# Remote_Core.net
KiCad netlist of a schematic drawn in Altium Designer
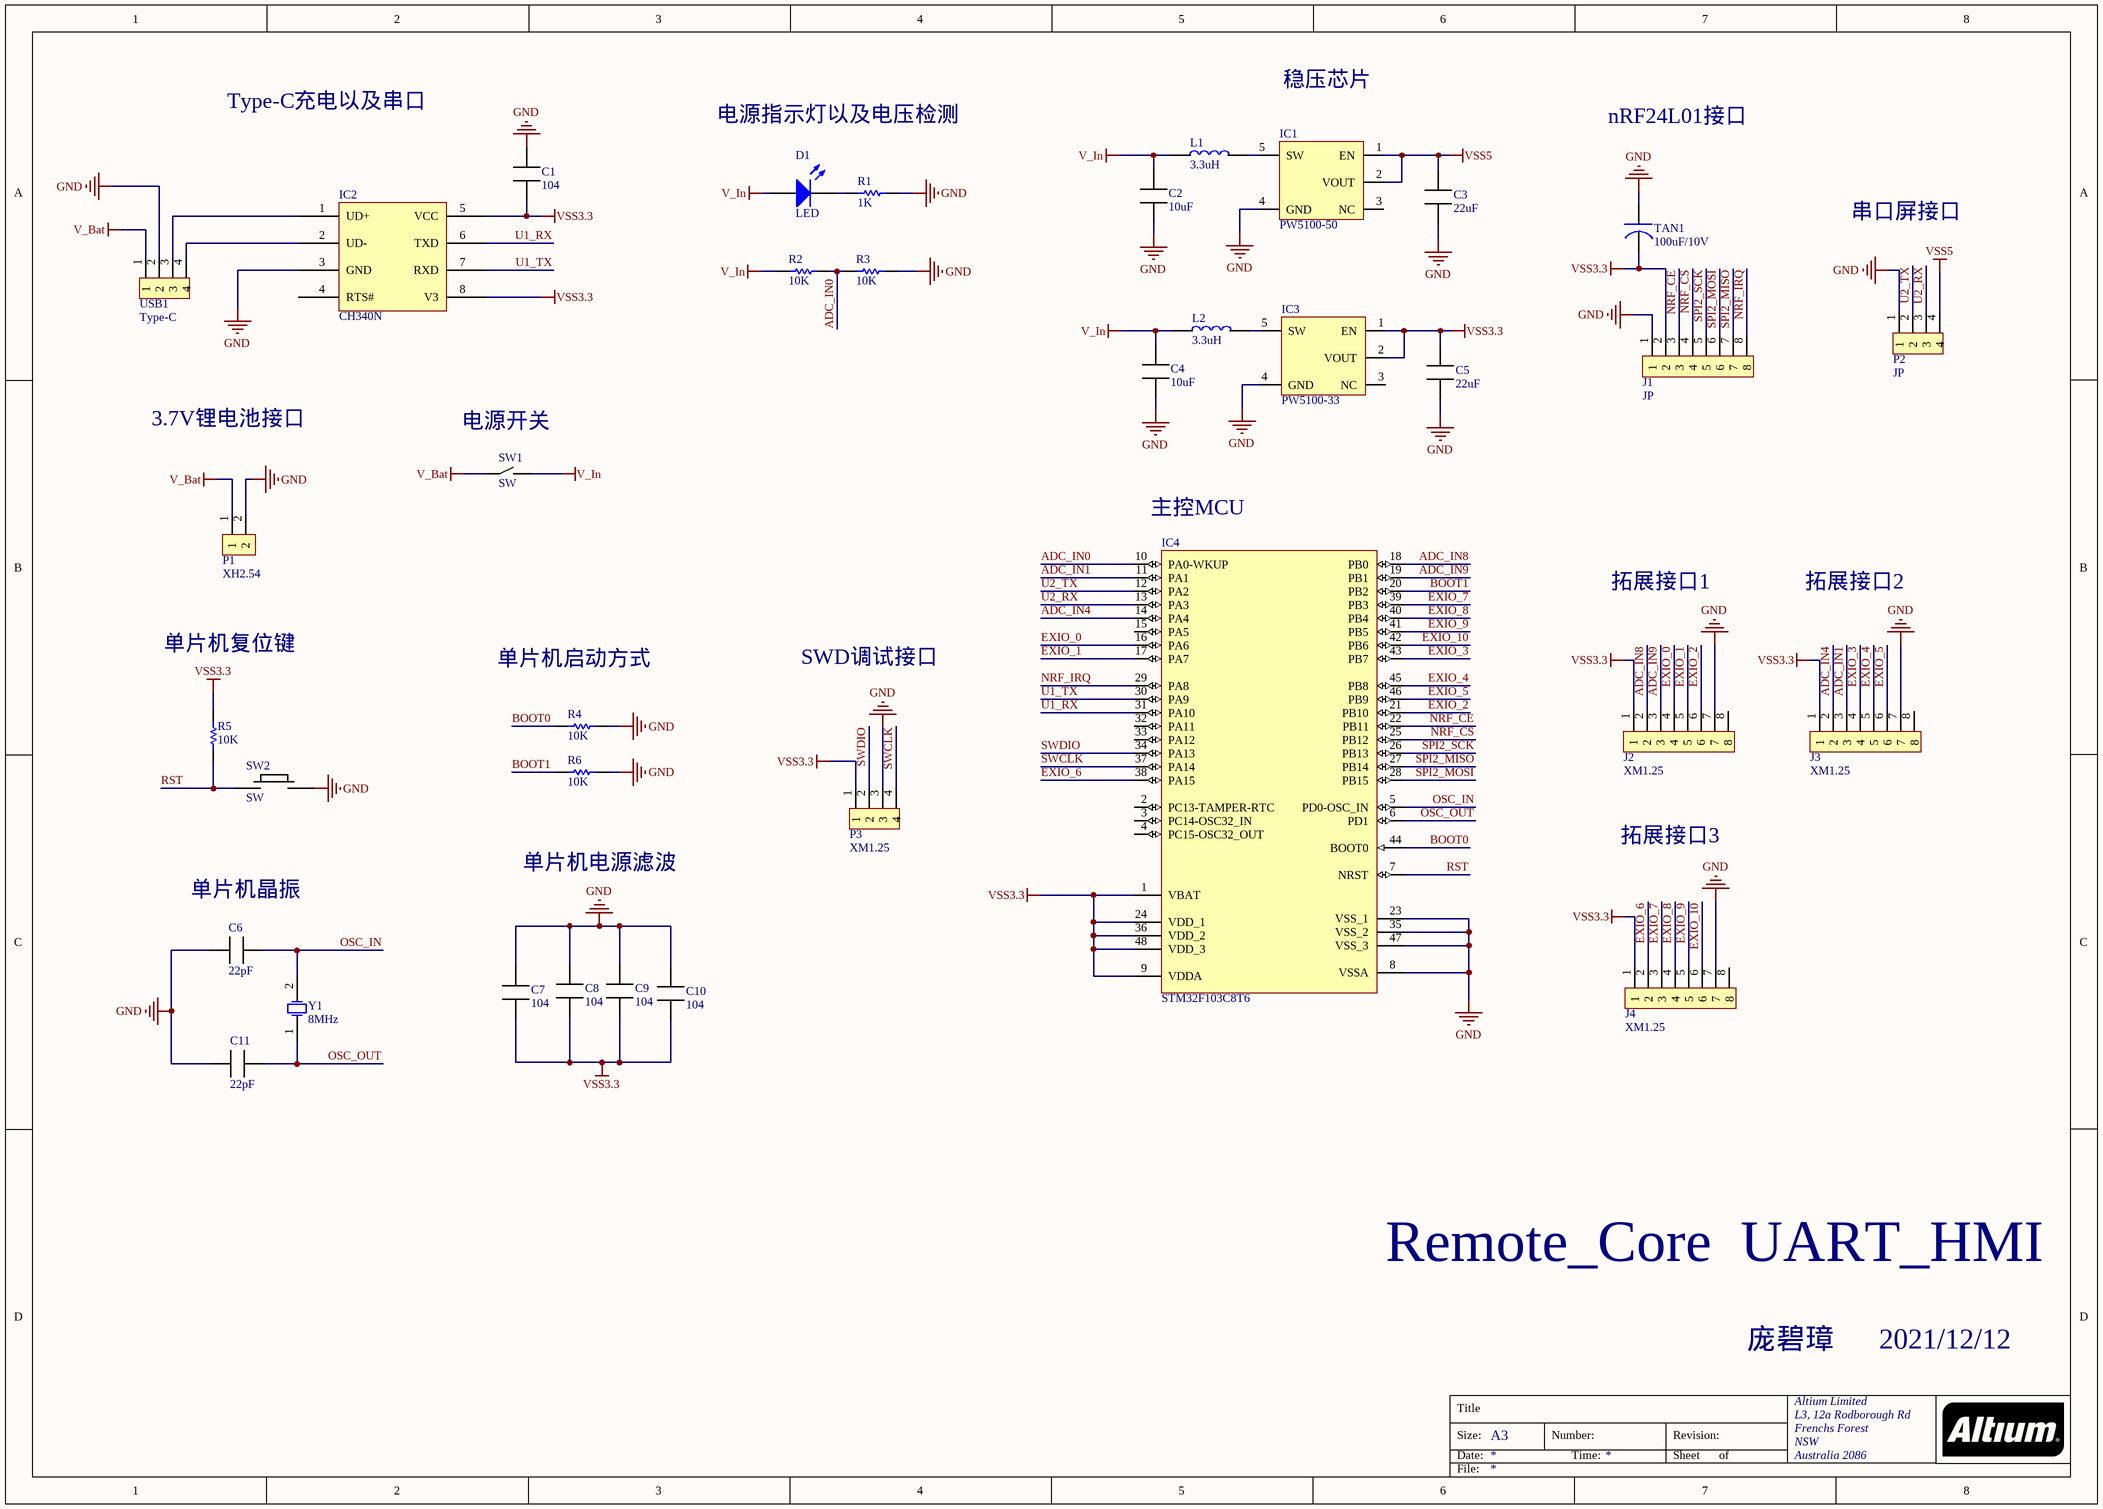
[diagram p0: Remote_Core.SchDoc]

(export (version "E")
  (design (tool "Eeschema 10.0.6"))
  (components
    (comp (ref "C1") (value "104") (footprint "C 0603") (libsource (lib "Remote") (part "电容")))
    (comp (ref "C2")
      (value "10uF")
      (footprint "C 0603")
      (libsource (lib "altium-import") (part "root_1_电容_"))
    )
    (comp (ref "C3") (value "22uF") (footprint "C 0603") (libsource (lib "Remote") (part "电容")))
    (comp (ref "C4")
      (value "10uF")
      (footprint "C 0603")
      (libsource (lib "altium-import") (part "root_1_电容_"))
    )
    (comp (ref "C5") (value "22uF") (footprint "C 0603") (libsource (lib "Remote") (part "电容")))
    (comp (ref "C6")
      (value "22pF")
      (footprint "C 0603")
      (libsource (lib "altium-import") (part "root_0_电容_"))
    )
    (comp (ref "C7") (value "104") (footprint "C 0603") (libsource (lib "Remote") (part "电容")))
    (comp (ref "C8") (value "104") (footprint "C 0603") (libsource (lib "Remote") (part "电容")))
    (comp (ref "C9") (value "104") (footprint "C 0603") (libsource (lib "Remote") (part "电容")))
    (comp (ref "C10") (value "104") (footprint "C 0603") (libsource (lib "Remote") (part "电容")))
    (comp (ref "C11")
      (value "22pF")
      (footprint "C 0603")
      (libsource (lib "altium-import") (part "root_0_电容_"))
    )
    (comp (ref "D1")
      (value "LED")
      (footprint "LED 0603")
      (description "Typical INFRARED GaAs LED")
      (fields (field (name "PUBLISHER") "Altium Limited"))
      (libsource (lib "Remote") (part "LED"))
    )
    (comp (ref "IC1")
      (value "PW5100-50")
      (footprint "PW5100")
      (libsource (lib "altium-import") (part "root_0_PW5100_"))
    )
    (comp (ref "IC2")
      (value "CH340N")
      (footprint "SOP-8")
      (libsource (lib "altium-import") (part "root_0_CH340N_"))
    )
    (comp (ref "IC3")
      (value "PW5100-33")
      (footprint "PW5100")
      (libsource (lib "altium-import") (part "root_0_PW5100_"))
    )
    (comp (ref "IC4")
      (value "STM32F103C8T6")
      (footprint "LQPF48 7X7")
      (libsource (lib "altium-import") (part "root_0_stm32f103c8t6_"))
    )
    (comp (ref "J1")
      (value "JP")
      (footprint "HDR2.54-LI-2x4P")
      (libsource (lib "altium-import") (part "root_0_1X8排针_"))
    )
    (comp (ref "J2")
      (value "XM1.25")
      (footprint "MX1.25 8P")
      (libsource (lib "altium-import") (part "root_0_1X8排针_"))
    )
    (comp (ref "J3")
      (value "XM1.25")
      (footprint "MX1.25 8P")
      (libsource (lib "altium-import") (part "root_0_1X8排针_"))
    )
    (comp (ref "J4")
      (value "XM1.25")
      (footprint "MX1.25 8P")
      (libsource (lib "altium-import") (part "root_0_1X8排针_"))
    )
    (comp (ref "L1") (value "3.3uH") (footprint "0630") (libsource (lib "Remote") (part "电感")))
    (comp (ref "L2") (value "3.3uH") (footprint "0630") (libsource (lib "Remote") (part "电感")))
    (comp (ref "P1") (value "XH2.54") (footprint "XH2.54 2P") (libsource (lib "Remote") (part "1X2排针")))
    (comp (ref "P2") (value "JP") (footprint "2.54 _ 4Pin") (libsource (lib "Remote") (part "1X4排针")))
    (comp (ref "P3")
      (value "XM1.25")
      (footprint "MX1.25")
      (libsource (lib "altium-import") (part "root_0_1X4排针_"))
    )
    (comp (ref "R1")
      (value "1K")
      (footprint "R 0603")
      (description "Resistor")
      (fields (field (name "PUBLISHER") "Altium Limited"))
      (libsource (lib "Remote") (part "Res"))
    )
    (comp (ref "R2")
      (value "10K")
      (footprint "R 0603")
      (description "Resistor")
      (fields (field (name "PUBLISHER") "Altium Limited"))
      (libsource (lib "Remote") (part "Res"))
    )
    (comp (ref "R3")
      (value "10K")
      (footprint "R 0603")
      (description "Resistor")
      (fields (field (name "PUBLISHER") "Altium Limited"))
      (libsource (lib "Remote") (part "Res"))
    )
    (comp (ref "R4")
      (value "10K")
      (footprint "R 0603")
      (description "Resistor")
      (fields (field (name "PUBLISHER") "Altium Limited"))
      (libsource (lib "altium-import") (part "root_0_Res_"))
    )
    (comp (ref "R5")
      (value "10K")
      (footprint "R 0603")
      (description "Resistor")
      (fields (field (name "PUBLISHER") "Altium Limited"))
      (libsource (lib "altium-import") (part "root_1_Res_"))
    )
    (comp (ref "R6")
      (value "10K")
      (footprint "R 0603")
      (description "Resistor")
      (fields (field (name "PUBLISHER") "Altium Limited"))
      (libsource (lib "altium-import") (part "root_0_Res_"))
    )
    (comp (ref "SW1") (value "SW") (footprint "拨动开关 9X3.5X3.5 侧卧") (libsource (lib "Remote") (part "开关")))
    (comp (ref "SW2")
      (value "SW")
      (footprint "SW SMD 3x6x2.5")
      (libsource (lib "altium-import") (part "root_0_弹簧开关_"))
    )
    (comp (ref "TAN1")
      (value "100uF/10V")
      (footprint "6.3*5.4mm 电解电容")
      (libsource (lib "Remote") (part "极性电容"))
    )
    (comp (ref "USB1")
      (value "Type-C")
      (footprint "USB Type-C")
      (libsource (lib "altium-import") (part "root_0_1X4排针_"))
    )
    (comp (ref "Y1")
      (value "8MHz")
      (footprint "OSC SMD")
      (description "Crystal Oscillator")
      (fields (field (name "PUBLISHER") "Altium Limited"))
      (libsource (lib "altium-import") (part "root_1_晶振_"))
    )
  )
  (nets
    (net (code "1") (name "/ADC_IN0") (class "Default")
      (node (ref "IC4") (pin "10") (pinfunction "PA0-WKUP_10") (pintype "bidirectional"))
      (node (ref "R2") (pin "2") (pinfunction "2_2") (pintype "passive"))
      (node (ref "R3") (pin "1") (pinfunction "1_1") (pintype "passive"))
    )
    (net (code "2") (name "/ADC_IN1") (class "Default")
      (node (ref "IC4") (pin "11") (pinfunction "PA1_11") (pintype "bidirectional"))
      (node (ref "J3") (pin "3") (pinfunction "3_3") (pintype "passive"))
    )
    (net (code "3") (name "/ADC_IN4") (class "Default")
      (node (ref "IC4") (pin "14") (pinfunction "PA4_14") (pintype "bidirectional"))
      (node (ref "J3") (pin "2") (pinfunction "2_2") (pintype "passive"))
    )
    (net (code "4") (name "/ADC_IN8") (class "Default")
      (node (ref "IC4") (pin "18") (pinfunction "PB0_18") (pintype "bidirectional"))
      (node (ref "J2") (pin "2") (pinfunction "2_2") (pintype "passive"))
    )
    (net (code "5") (name "/ADC_IN9") (class "Default")
      (node (ref "IC4") (pin "19") (pinfunction "PB1_19") (pintype "bidirectional"))
      (node (ref "J2") (pin "3") (pinfunction "3_3") (pintype "passive"))
    )
    (net (code "6") (name "/BOOT0") (class "Default")
      (node (ref "IC4") (pin "44") (pinfunction "BOOT0_44") (pintype "input"))
      (node (ref "R4") (pin "1") (pinfunction "1_1") (pintype "passive"))
    )
    (net (code "7") (name "/BOOT1") (class "Default")
      (node (ref "IC4") (pin "20") (pinfunction "PB2_20") (pintype "bidirectional"))
      (node (ref "R6") (pin "1") (pinfunction "1_1") (pintype "passive"))
    )
    (net (code "8") (name "/EXIO_0") (class "Default")
      (node (ref "IC4") (pin "16") (pinfunction "PA6_16") (pintype "bidirectional"))
      (node (ref "J2") (pin "4") (pinfunction "4_4") (pintype "passive"))
    )
    (net (code "9") (name "/EXIO_1") (class "Default")
      (node (ref "IC4") (pin "17") (pinfunction "PA7_17") (pintype "bidirectional"))
      (node (ref "J2") (pin "5") (pinfunction "5_5") (pintype "passive"))
    )
    (net (code "10") (name "/EXIO_2") (class "Default")
      (node (ref "IC4") (pin "21") (pinfunction "PB10_21") (pintype "bidirectional"))
      (node (ref "J2") (pin "6") (pinfunction "6_6") (pintype "passive"))
    )
    (net (code "11") (name "/EXIO_3") (class "Default")
      (node (ref "IC4") (pin "43") (pinfunction "PB7_43") (pintype "bidirectional"))
      (node (ref "J3") (pin "4") (pinfunction "4_4") (pintype "passive"))
    )
    (net (code "12") (name "/EXIO_4") (class "Default")
      (node (ref "IC4") (pin "45") (pinfunction "PB8_45") (pintype "bidirectional"))
      (node (ref "J3") (pin "5") (pinfunction "5_5") (pintype "passive"))
    )
    (net (code "13") (name "/EXIO_5") (class "Default")
      (node (ref "IC4") (pin "46") (pinfunction "PB9_46") (pintype "bidirectional"))
      (node (ref "J3") (pin "6") (pinfunction "6_6") (pintype "passive"))
    )
    (net (code "14") (name "/EXIO_6") (class "Default")
      (node (ref "IC4") (pin "38") (pinfunction "PA15_38") (pintype "bidirectional"))
      (node (ref "J4") (pin "2") (pinfunction "2_2") (pintype "passive"))
    )
    (net (code "15") (name "/EXIO_7") (class "Default")
      (node (ref "IC4") (pin "39") (pinfunction "PB3_39") (pintype "bidirectional"))
      (node (ref "J4") (pin "3") (pinfunction "3_3") (pintype "passive"))
    )
    (net (code "16") (name "/EXIO_8") (class "Default")
      (node (ref "IC4") (pin "40") (pinfunction "PB4_40") (pintype "bidirectional"))
      (node (ref "J4") (pin "4") (pinfunction "4_4") (pintype "passive"))
    )
    (net (code "17") (name "/EXIO_9") (class "Default")
      (node (ref "IC4") (pin "41") (pinfunction "PB5_41") (pintype "bidirectional"))
      (node (ref "J4") (pin "5") (pinfunction "5_5") (pintype "passive"))
    )
    (net (code "18") (name "/EXIO_10") (class "Default")
      (node (ref "IC4") (pin "42") (pinfunction "PB6_42") (pintype "bidirectional"))
      (node (ref "J4") (pin "6") (pinfunction "6_6") (pintype "passive"))
    )
    (net (code "19") (name "/NRF_CE") (class "Default")
      (node (ref "IC4") (pin "22") (pinfunction "PB11_22") (pintype "bidirectional"))
      (node (ref "J1") (pin "3") (pinfunction "3_3") (pintype "passive"))
    )
    (net (code "20") (name "/NRF_CS") (class "Default")
      (node (ref "IC4") (pin "25") (pinfunction "PB12_25") (pintype "bidirectional"))
      (node (ref "J1") (pin "4") (pinfunction "4_4") (pintype "passive"))
    )
    (net (code "21") (name "/NRF_IRQ") (class "Default")
      (node (ref "IC4") (pin "29") (pinfunction "PA8_29") (pintype "bidirectional"))
      (node (ref "J1") (pin "8") (pinfunction "8_8") (pintype "passive"))
    )
    (net (code "22") (name "/OSC_IN") (class "Default")
      (node (ref "C6") (pin "2") (pinfunction "2_2") (pintype "passive"))
      (node (ref "IC4") (pin "5") (pinfunction "PD0-OSC_IN_5") (pintype "bidirectional"))
      (node (ref "Y1") (pin "2") (pinfunction "OSC2_2") (pintype "passive"))
    )
    (net (code "23") (name "/OSC_OUT") (class "Default")
      (node (ref "C11") (pin "2") (pinfunction "2_2") (pintype "passive"))
      (node (ref "IC4") (pin "6") (pinfunction "PD1_6") (pintype "bidirectional"))
      (node (ref "Y1") (pin "1") (pinfunction "OSC1_1") (pintype "passive"))
    )
    (net (code "24") (name "/RST") (class "Default")
      (node (ref "IC4") (pin "7") (pinfunction "NRST_7") (pintype "bidirectional"))
      (node (ref "R5") (pin "1") (pinfunction "1_1") (pintype "passive"))
      (node (ref "SW2") (pin "1") (pinfunction "1_1") (pintype "passive"))
    )
    (net (code "25") (name "/SPI2_MISO") (class "Default")
      (node (ref "IC4") (pin "27") (pinfunction "PB14_27") (pintype "bidirectional"))
      (node (ref "J1") (pin "7") (pinfunction "7_7") (pintype "passive"))
    )
    (net (code "26") (name "/SPI2_MOSI") (class "Default")
      (node (ref "IC4") (pin "28") (pinfunction "PB15_28") (pintype "bidirectional"))
      (node (ref "J1") (pin "6") (pinfunction "6_6") (pintype "passive"))
    )
    (net (code "27") (name "/SPI2_SCK") (class "Default")
      (node (ref "IC4") (pin "26") (pinfunction "PB13_26") (pintype "bidirectional"))
      (node (ref "J1") (pin "5") (pinfunction "5_5") (pintype "passive"))
    )
    (net (code "28") (name "/SWCLK") (class "Default")
      (node (ref "IC4") (pin "37") (pinfunction "PA14_37") (pintype "bidirectional"))
      (node (ref "P3") (pin "4") (pinfunction "4_4") (pintype "passive"))
    )
    (net (code "29") (name "/SWDIO") (class "Default")
      (node (ref "IC4") (pin "34") (pinfunction "PA13_34") (pintype "bidirectional"))
      (node (ref "P3") (pin "2") (pinfunction "2_2") (pintype "passive"))
    )
    (net (code "30") (name "/U1_RX") (class "Default")
      (node (ref "IC2") (pin "6") (pinfunction "TXD_6") (pintype "passive"))
      (node (ref "IC4") (pin "31") (pinfunction "PA10_31") (pintype "bidirectional"))
    )
    (net (code "31") (name "/U1_TX") (class "Default")
      (node (ref "IC2") (pin "7") (pinfunction "RXD_7") (pintype "passive"))
      (node (ref "IC4") (pin "30") (pinfunction "PA9_30") (pintype "bidirectional"))
    )
    (net (code "32") (name "/U2_RX") (class "Default")
      (node (ref "IC4") (pin "13") (pinfunction "PA3_13") (pintype "bidirectional"))
      (node (ref "P2") (pin "3") (pinfunction "3_3") (pintype "passive"))
    )
    (net (code "33") (name "/U2_TX") (class "Default")
      (node (ref "IC4") (pin "12") (pinfunction "PA2_12") (pintype "bidirectional"))
      (node (ref "P2") (pin "2") (pinfunction "2_2") (pintype "passive"))
    )
    (net (code "34") (name "GND") (class "Default")
      (node (ref "C1") (pin "2") (pinfunction "2_2") (pintype "passive"))
      (node (ref "C10") (pin "2") (pinfunction "2_2") (pintype "passive"))
      (node (ref "C11") (pin "1") (pinfunction "1_1") (pintype "passive"))
      (node (ref "C2") (pin "1") (pinfunction "1_1") (pintype "passive"))
      (node (ref "C3") (pin "1") (pinfunction "1_1") (pintype "passive"))
      (node (ref "C4") (pin "1") (pinfunction "1_1") (pintype "passive"))
      (node (ref "C5") (pin "1") (pinfunction "1_1") (pintype "passive"))
      (node (ref "C6") (pin "1") (pinfunction "1_1") (pintype "passive"))
      (node (ref "C7") (pin "2") (pinfunction "2_2") (pintype "passive"))
      (node (ref "C8") (pin "2") (pinfunction "2_2") (pintype "passive"))
      (node (ref "C9") (pin "2") (pinfunction "2_2") (pintype "passive"))
      (node (ref "IC1") (pin "4") (pinfunction "GND_4") (pintype "passive"))
      (node (ref "IC2") (pin "3") (pinfunction "GND_3") (pintype "passive"))
      (node (ref "IC3") (pin "4") (pinfunction "GND_4") (pintype "passive"))
      (node (ref "IC4") (pin "23") (pinfunction "VSS_1_23") (pintype "power_in"))
      (node (ref "IC4") (pin "35") (pinfunction "VSS_2_35") (pintype "power_in"))
      (node (ref "IC4") (pin "47") (pinfunction "VSS_3_47") (pintype "power_in"))
      (node (ref "IC4") (pin "8") (pinfunction "VSSA_8") (pintype "power_in"))
      (node (ref "J1") (pin "1") (pinfunction "1_1") (pintype "passive"))
      (node (ref "J2") (pin "7") (pinfunction "7_7") (pintype "passive"))
      (node (ref "J3") (pin "7") (pinfunction "7_7") (pintype "passive"))
      (node (ref "J4") (pin "7") (pinfunction "7_7") (pintype "passive"))
      (node (ref "P1") (pin "2") (pinfunction "2_2") (pintype "passive"))
      (node (ref "P2") (pin "1") (pinfunction "1_1") (pintype "passive"))
      (node (ref "P3") (pin "3") (pinfunction "3_3") (pintype "passive"))
      (node (ref "R1") (pin "2") (pinfunction "2_2") (pintype "passive"))
      (node (ref "R3") (pin "2") (pinfunction "2_2") (pintype "passive"))
      (node (ref "R4") (pin "2") (pinfunction "2_2") (pintype "passive"))
      (node (ref "R6") (pin "2") (pinfunction "2_2") (pintype "passive"))
      (node (ref "SW2") (pin "2") (pinfunction "2_2") (pintype "passive"))
      (node (ref "TAN1") (pin "2") (pinfunction "2_2") (pintype "passive"))
      (node (ref "USB1") (pin "2") (pinfunction "2_2") (pintype "passive"))
    )
    (net (code "35") (name "Net-(D1-K)") (class "Default")
      (node (ref "D1") (pin "2") (pinfunction "K_2") (pintype "passive"))
      (node (ref "R1") (pin "1") (pinfunction "1_1") (pintype "passive"))
    )
    (net (code "36") (name "Net-(IC1-SW)") (class "Default")
      (node (ref "IC1") (pin "5") (pinfunction "SW_5") (pintype "passive"))
      (node (ref "L1") (pin "2") (pinfunction "2_2") (pintype "passive"))
    )
    (net (code "37") (name "Net-(IC2-UD+)") (class "Default")
      (node (ref "IC2") (pin "1") (pinfunction "UD+_1") (pintype "passive"))
      (node (ref "USB1") (pin "3") (pinfunction "3_3") (pintype "passive"))
    )
    (net (code "38") (name "Net-(IC2-UD-)") (class "Default")
      (node (ref "IC2") (pin "2") (pinfunction "UD-_2") (pintype "passive"))
      (node (ref "USB1") (pin "4") (pinfunction "4_4") (pintype "passive"))
    )
    (net (code "39") (name "Net-(IC3-SW)") (class "Default")
      (node (ref "IC3") (pin "5") (pinfunction "SW_5") (pintype "passive"))
      (node (ref "L2") (pin "2") (pinfunction "2_2") (pintype "passive"))
    )
    (net (code "40") (name "VSS3.3") (class "Default")
      (node (ref "C1") (pin "1") (pinfunction "1_1") (pintype "passive"))
      (node (ref "C10") (pin "1") (pinfunction "1_1") (pintype "passive"))
      (node (ref "C5") (pin "2") (pinfunction "2_2") (pintype "passive"))
      (node (ref "C7") (pin "1") (pinfunction "1_1") (pintype "passive"))
      (node (ref "C8") (pin "1") (pinfunction "1_1") (pintype "passive"))
      (node (ref "C9") (pin "1") (pinfunction "1_1") (pintype "passive"))
      (node (ref "IC2") (pin "5") (pinfunction "VCC_5") (pintype "passive"))
      (node (ref "IC2") (pin "8") (pinfunction "V3_8") (pintype "passive"))
      (node (ref "IC3") (pin "1") (pinfunction "EN_1") (pintype "passive"))
      (node (ref "IC3") (pin "2") (pinfunction "VOUT_2") (pintype "passive"))
      (node (ref "IC4") (pin "1") (pinfunction "VBAT_1") (pintype "power_in"))
      (node (ref "IC4") (pin "24") (pinfunction "VDD_1_24") (pintype "power_in"))
      (node (ref "IC4") (pin "36") (pinfunction "VDD_2_36") (pintype "power_in"))
      (node (ref "IC4") (pin "48") (pinfunction "VDD_3_48") (pintype "power_in"))
      (node (ref "IC4") (pin "9") (pinfunction "VDDA_9") (pintype "power_in"))
      (node (ref "J1") (pin "2") (pinfunction "2_2") (pintype "passive"))
      (node (ref "J2") (pin "1") (pinfunction "1_1") (pintype "passive"))
      (node (ref "J3") (pin "1") (pinfunction "1_1") (pintype "passive"))
      (node (ref "J4") (pin "1") (pinfunction "1_1") (pintype "passive"))
      (node (ref "P3") (pin "1") (pinfunction "1_1") (pintype "passive"))
      (node (ref "R5") (pin "2") (pinfunction "2_2") (pintype "passive"))
      (node (ref "TAN1") (pin "1") (pinfunction "1_1") (pintype "passive"))
    )
    (net (code "41") (name "VSS5") (class "Default")
      (node (ref "C3") (pin "2") (pinfunction "2_2") (pintype "passive"))
      (node (ref "IC1") (pin "1") (pinfunction "EN_1") (pintype "passive"))
      (node (ref "IC1") (pin "2") (pinfunction "VOUT_2") (pintype "passive"))
      (node (ref "P2") (pin "4") (pinfunction "4_4") (pintype "passive"))
    )
    (net (code "42") (name "V_Bat") (class "Default")
      (node (ref "P1") (pin "1") (pinfunction "1_1") (pintype "passive"))
      (node (ref "SW1") (pin "2") (pinfunction "2_2") (pintype "passive"))
      (node (ref "USB1") (pin "1") (pinfunction "1_1") (pintype "passive"))
    )
    (net (code "43") (name "V_In") (class "Default")
      (node (ref "C2") (pin "2") (pinfunction "2_2") (pintype "passive"))
      (node (ref "C4") (pin "2") (pinfunction "2_2") (pintype "passive"))
      (node (ref "D1") (pin "1") (pinfunction "A_1") (pintype "passive"))
      (node (ref "L1") (pin "1") (pinfunction "1_1") (pintype "passive"))
      (node (ref "L2") (pin "1") (pinfunction "1_1") (pintype "passive"))
      (node (ref "R2") (pin "1") (pinfunction "1_1") (pintype "passive"))
      (node (ref "SW1") (pin "1") (pinfunction "1_1") (pintype "passive"))
    )
    (net (code "44") (name "unconnected-(IC1-NC-Pad3)") (class "Default")
      (node (ref "IC1") (pin "3") (pinfunction "NC_3") (pintype "passive"))
    )
    (net (code "45") (name "unconnected-(IC2-RTS#-Pad4)") (class "Default")
      (node (ref "IC2") (pin "4") (pinfunction "RTS#_4") (pintype "passive"))
    )
    (net (code "46") (name "unconnected-(IC3-NC-Pad3)") (class "Default")
      (node (ref "IC3") (pin "3") (pinfunction "NC_3") (pintype "passive"))
    )
    (net (code "47") (name "unconnected-(IC4-PA5-Pad15)") (class "Default")
      (node (ref "IC4") (pin "15") (pinfunction "PA5_15") (pintype "bidirectional"))
    )
    (net (code "48") (name "unconnected-(IC4-PA11-Pad32)") (class "Default")
      (node (ref "IC4") (pin "32") (pinfunction "PA11_32") (pintype "bidirectional"))
    )
    (net (code "49") (name "unconnected-(IC4-PA12-Pad33)") (class "Default")
      (node (ref "IC4") (pin "33") (pinfunction "PA12_33") (pintype "bidirectional"))
    )
    (net (code "50") (name "unconnected-(IC4-PC13-TAMPER-RTC-Pad2)") (class "Default")
      (node (ref "IC4") (pin "2") (pinfunction "PC13-TAMPER-RTC_2") (pintype "bidirectional"))
    )
    (net (code "51") (name "unconnected-(IC4-PC14-OSC32_IN-Pad3)") (class "Default")
      (node (ref "IC4") (pin "3") (pinfunction "PC14-OSC32_IN_3") (pintype "bidirectional"))
    )
    (net (code "52") (name "unconnected-(IC4-PC15-OSC32_OUT-Pad4)") (class "Default")
      (node (ref "IC4") (pin "4") (pinfunction "PC15-OSC32_OUT_4") (pintype "bidirectional"))
    )
    (net (code "53") (name "unconnected-(J2-Pad8)") (class "Default")
      (node (ref "J2") (pin "8") (pinfunction "8_8") (pintype "passive"))
    )
    (net (code "54") (name "unconnected-(J3-Pad8)") (class "Default")
      (node (ref "J3") (pin "8") (pinfunction "8_8") (pintype "passive"))
    )
    (net (code "55") (name "unconnected-(J4-Pad8)") (class "Default")
      (node (ref "J4") (pin "8") (pinfunction "8_8") (pintype "passive"))
    )
  )
)
